# Power.net
KiCad netlist of a schematic drawn in Altium Designer
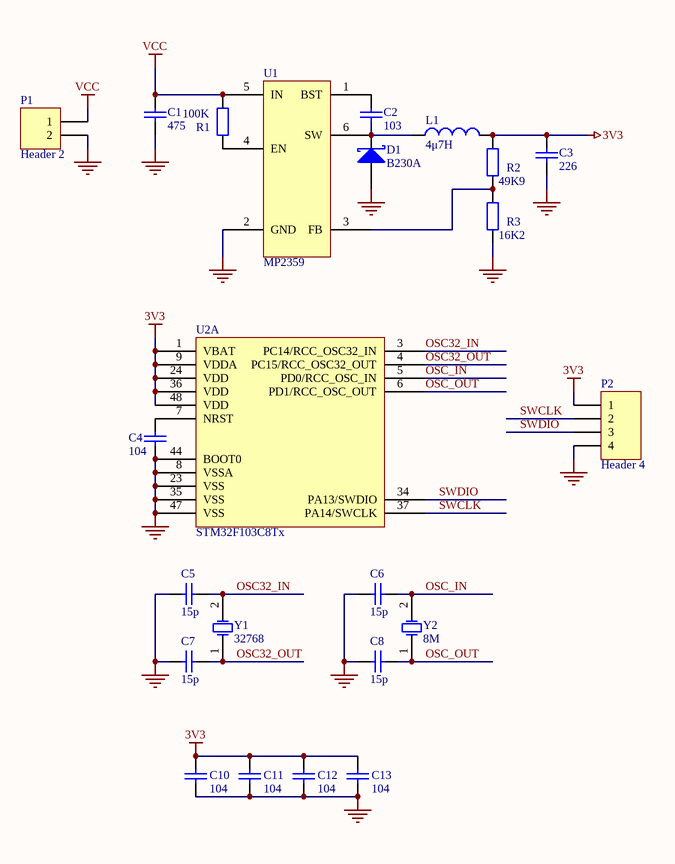
[diagram p0: Power.SchDoc]

(export (version "E")
  (design (tool "Eeschema 10.0.6"))
  (components
    (comp (ref "C1")
      (value "475")
      (footprint "MicroControl:C1206")
      (description "Capacitor")
      (fields (field (name "PUBLISHER") "Altium Limited"))
      (libsource (lib "Miscellaneous Devices") (part "Cap"))
    )
    (comp (ref "C2")
      (value "103")
      (footprint "MicroControl:C0603")
      (description "Capacitor")
      (fields (field (name "PUBLISHER") "Altium Limited"))
      (libsource (lib "Miscellaneous Devices") (part "Cap"))
    )
    (comp (ref "C3")
      (value "226")
      (footprint "MicroControl:C0805")
      (description "Capacitor")
      (fields (field (name "PUBLISHER") "Altium Limited"))
      (libsource (lib "Miscellaneous Devices") (part "Cap"))
    )
    (comp (ref "C4")
      (value "104")
      (footprint "MicroControl:C0603")
      (description "Capacitor")
      (fields (field (name "PUBLISHER") "Altium Limited"))
      (libsource (lib "Miscellaneous Devices") (part "Cap"))
    )
    (comp (ref "C5")
      (value "15p")
      (footprint "MicroControl:C0603")
      (description "Capacitor")
      (fields (field (name "PUBLISHER") "Altium Limited"))
      (libsource (lib "Miscellaneous Devices") (part "Cap"))
    )
    (comp (ref "C6")
      (value "15p")
      (footprint "MicroControl:C0603")
      (description "Capacitor")
      (fields (field (name "PUBLISHER") "Altium Limited"))
      (libsource (lib "Miscellaneous Devices") (part "Cap"))
    )
    (comp (ref "C7")
      (value "15p")
      (footprint "MicroControl:C0603")
      (description "Capacitor")
      (fields (field (name "PUBLISHER") "Altium Limited"))
      (libsource (lib "Miscellaneous Devices") (part "Cap"))
    )
    (comp (ref "C8")
      (value "15p")
      (footprint "MicroControl:C0603")
      (description "Capacitor")
      (fields (field (name "PUBLISHER") "Altium Limited"))
      (libsource (lib "Miscellaneous Devices") (part "Cap"))
    )
    (comp (ref "C10")
      (value "104")
      (footprint "MicroControl:C0603")
      (description "Capacitor")
      (fields (field (name "PUBLISHER") "Altium Limited"))
      (libsource (lib "Miscellaneous Devices") (part "Cap"))
    )
    (comp (ref "C11")
      (value "104")
      (footprint "MicroControl:C0603")
      (description "Capacitor")
      (fields (field (name "PUBLISHER") "Altium Limited"))
      (libsource (lib "Miscellaneous Devices") (part "Cap"))
    )
    (comp (ref "C12")
      (value "104")
      (footprint "MicroControl:C0603")
      (description "Capacitor")
      (fields (field (name "PUBLISHER") "Altium Limited"))
      (libsource (lib "Miscellaneous Devices") (part "Cap"))
    )
    (comp (ref "C13")
      (value "104")
      (footprint "MicroControl:C0603")
      (description "Capacitor")
      (fields (field (name "PUBLISHER") "Altium Limited"))
      (libsource (lib "Miscellaneous Devices") (part "Cap"))
    )
    (comp (ref "D1")
      (value "B230A")
      (footprint "MicroControl:SMA")
      (description "Silicon AF Schottky Diode for High-Speed Switching")
      (fields (field (name "PUBLISHER") "Altium Limited"))
      (libsource (lib "Miscellaneous Devices") (part "Diode BAS70"))
    )
    (comp (ref "L1")
      (value "4μ7H")
      (footprint "MicroControl:L4X4")
      (fields (field (name "PUBLISHER") "Altium Limited"))
      (libsource (lib "Miscellaneous Devices") (part "Inductor"))
    )
    (comp (ref "P1")
      (value "Header 2")
      (footprint "Connetor:XH2P54P2")
      (description "Header, 2-Pin, Right Angle")
      (fields (field (name "PUBLISHER") "Altium Limited"))
      (libsource (lib "Miscellaneous Connectors") (part "Header 2H"))
    )
    (comp (ref "P2")
      (value "Header 4")
      (footprint "Connetor:SIP4")
      (description "Header, 4-Pin")
      (fields (field (name "PUBLISHER") "Altium Limited"))
      (libsource (lib "Miscellaneous Connectors") (part "Header 4"))
    )
    (comp (ref "R1")
      (value "100K")
      (footprint "MicroControl:R0603")
      (description "Resistor")
      (fields (field (name "PUBLISHER") "Altium Limited"))
      (libsource (lib "Miscellaneous Devices") (part "Res2"))
    )
    (comp (ref "R2")
      (value "49K9")
      (footprint "MicroControl:R0603")
      (description "Resistor")
      (fields (field (name "PUBLISHER") "Altium Limited"))
      (libsource (lib "Miscellaneous Devices") (part "Res2"))
    )
    (comp (ref "R3")
      (value "16K2")
      (footprint "MicroControl:R0603")
      (description "Resistor")
      (fields (field (name "PUBLISHER") "Altium Limited"))
      (libsource (lib "Miscellaneous Devices") (part "Res2"))
    )
    (comp (ref "U1") (value "MP2359") (footprint "SOT23-6") (libsource (lib "yinhaonanLib") (part "MP2359")))
    (comp (ref "U2")
      (value "STM32F103C8Tx")
      (footprint "Integrated_Circuit:PQFP48")
      (libsource (lib "yinhaonanLib") (part "STM32F103C8Tx"))
    )
    (comp (ref "Y1")
      (value "32768")
      (footprint "MicroControl:FC-135")
      (description "Crystal Oscillator")
      (fields (field (name "PUBLISHER") "Altium Limited"))
      (libsource (lib "Miscellaneous Devices") (part "XTAL"))
    )
    (comp (ref "Y2")
      (value "8M")
      (footprint "MicroControl:CY5032")
      (description "Crystal Oscillator")
      (fields (field (name "PUBLISHER") "Altium Limited"))
      (libsource (lib "Miscellaneous Devices") (part "XTAL"))
    )
  )
  (nets
    (net (code "1") (name "/OSC32_IN") (class "Default")
      (node (ref "C5") (pin "1") (pinfunction "1_1") (pintype "passive"))
      (node (ref "U2") (pin "3") (pinfunction "PC14/RCC_OSC32_IN_3") (pintype "passive"))
      (node (ref "Y1") (pin "2") (pinfunction "OSC2_2") (pintype "passive"))
    )
    (net (code "2") (name "/OSC32_OUT") (class "Default")
      (node (ref "C7") (pin "1") (pinfunction "1_1") (pintype "passive"))
      (node (ref "U2") (pin "4") (pinfunction "PC15/RCC_OSC32_OUT_4") (pintype "passive"))
      (node (ref "Y1") (pin "1") (pinfunction "OSC1_1") (pintype "passive"))
    )
    (net (code "3") (name "/OSC_IN") (class "Default")
      (node (ref "C6") (pin "1") (pinfunction "1_1") (pintype "passive"))
      (node (ref "U2") (pin "5") (pinfunction "PD0/RCC_OSC_IN_5") (pintype "passive"))
      (node (ref "Y2") (pin "2") (pinfunction "OSC2_2") (pintype "passive"))
    )
    (net (code "4") (name "/OSC_OUT") (class "Default")
      (node (ref "C8") (pin "1") (pinfunction "1_1") (pintype "passive"))
      (node (ref "U2") (pin "6") (pinfunction "PD1/RCC_OSC_OUT_6") (pintype "passive"))
      (node (ref "Y2") (pin "1") (pinfunction "OSC1_1") (pintype "passive"))
    )
    (net (code "5") (name "/SWCLK") (class "Default")
      (node (ref "P2") (pin "2") (pinfunction "2_2") (pintype "passive"))
      (node (ref "U2") (pin "37") (pinfunction "PA14/SWCLK_37") (pintype "passive"))
    )
    (net (code "6") (name "/SWDIO") (class "Default")
      (node (ref "P2") (pin "3") (pinfunction "3_3") (pintype "passive"))
      (node (ref "U2") (pin "34") (pinfunction "PA13/SWDIO_34") (pintype "passive"))
    )
    (net (code "7") (name "3V3") (class "Default")
      (node (ref "C10") (pin "2") (pinfunction "2_2") (pintype "passive"))
      (node (ref "C11") (pin "2") (pinfunction "2_2") (pintype "passive"))
      (node (ref "C12") (pin "2") (pinfunction "2_2") (pintype "passive"))
      (node (ref "C13") (pin "2") (pinfunction "2_2") (pintype "passive"))
      (node (ref "C3") (pin "2") (pinfunction "2_2") (pintype "passive"))
      (node (ref "L1") (pin "2") (pinfunction "2_2") (pintype "passive"))
      (node (ref "P2") (pin "1") (pinfunction "1_1") (pintype "passive"))
      (node (ref "R2") (pin "1") (pinfunction "1_1") (pintype "passive"))
      (node (ref "U2") (pin "1") (pinfunction "VBAT_1") (pintype "passive"))
      (node (ref "U2") (pin "24") (pinfunction "VDD_24") (pintype "passive"))
      (node (ref "U2") (pin "36") (pinfunction "VDD_36") (pintype "passive"))
      (node (ref "U2") (pin "48") (pinfunction "VDD_48") (pintype "passive"))
      (node (ref "U2") (pin "9") (pinfunction "VDDA_9") (pintype "passive"))
    )
    (net (code "8") (name "GND") (class "Default")
      (node (ref "C1") (pin "1") (pinfunction "1_1") (pintype "passive"))
      (node (ref "C10") (pin "1") (pinfunction "1_1") (pintype "passive"))
      (node (ref "C11") (pin "1") (pinfunction "1_1") (pintype "passive"))
      (node (ref "C12") (pin "1") (pinfunction "1_1") (pintype "passive"))
      (node (ref "C13") (pin "1") (pinfunction "1_1") (pintype "passive"))
      (node (ref "C3") (pin "1") (pinfunction "1_1") (pintype "passive"))
      (node (ref "C4") (pin "1") (pinfunction "1_1") (pintype "passive"))
      (node (ref "C5") (pin "2") (pinfunction "2_2") (pintype "passive"))
      (node (ref "C6") (pin "2") (pinfunction "2_2") (pintype "passive"))
      (node (ref "C7") (pin "2") (pinfunction "2_2") (pintype "passive"))
      (node (ref "C8") (pin "2") (pinfunction "2_2") (pintype "passive"))
      (node (ref "D1") (pin "1") (pinfunction "A_1") (pintype "passive"))
      (node (ref "P1") (pin "2") (pinfunction "2_2") (pintype "passive"))
      (node (ref "P2") (pin "4") (pinfunction "4_4") (pintype "passive"))
      (node (ref "R3") (pin "2") (pinfunction "2_2") (pintype "passive"))
      (node (ref "U1") (pin "2") (pinfunction "GND_2") (pintype "passive"))
      (node (ref "U2") (pin "23") (pinfunction "VSS_23") (pintype "passive"))
      (node (ref "U2") (pin "35") (pinfunction "VSS_35") (pintype "passive"))
      (node (ref "U2") (pin "44") (pinfunction "BOOT0_44") (pintype "passive"))
      (node (ref "U2") (pin "47") (pinfunction "VSS_47") (pintype "passive"))
      (node (ref "U2") (pin "8") (pinfunction "VSSA_8") (pintype "passive"))
    )
    (net (code "9") (name "Net-(D1-K)") (class "Default")
      (node (ref "C2") (pin "1") (pinfunction "1_1") (pintype "passive"))
      (node (ref "D1") (pin "2") (pinfunction "K_2") (pintype "passive"))
      (node (ref "L1") (pin "1") (pinfunction "1_1") (pintype "passive"))
      (node (ref "U1") (pin "6") (pinfunction "SW_6") (pintype "passive"))
    )
    (net (code "10") (name "Net-(U1-BST)") (class "Default")
      (node (ref "C2") (pin "2") (pinfunction "2_2") (pintype "passive"))
      (node (ref "U1") (pin "1") (pinfunction "BST_1") (pintype "passive"))
    )
    (net (code "11") (name "Net-(U1-EN)") (class "Default")
      (node (ref "R1") (pin "2") (pinfunction "2_2") (pintype "passive"))
      (node (ref "U1") (pin "4") (pinfunction "EN_4") (pintype "passive"))
    )
    (net (code "12") (name "Net-(U1-FB)") (class "Default")
      (node (ref "R2") (pin "2") (pinfunction "2_2") (pintype "passive"))
      (node (ref "R3") (pin "1") (pinfunction "1_1") (pintype "passive"))
      (node (ref "U1") (pin "3") (pinfunction "FB_3") (pintype "passive"))
    )
    (net (code "13") (name "Net-(U2A-NRST)") (class "Default")
      (node (ref "C4") (pin "2") (pinfunction "2_2") (pintype "passive"))
      (node (ref "U2") (pin "7") (pinfunction "NRST_7") (pintype "passive"))
    )
    (net (code "14") (name "VCC") (class "Default")
      (node (ref "C1") (pin "2") (pinfunction "2_2") (pintype "passive"))
      (node (ref "P1") (pin "1") (pinfunction "1_1") (pintype "passive"))
      (node (ref "R1") (pin "1") (pinfunction "1_1") (pintype "passive"))
      (node (ref "U1") (pin "5") (pinfunction "IN_5") (pintype "passive"))
    )
  )
)
